# LED_ARRAY.net
KiCad netlist of a schematic drawn in Altium Designer
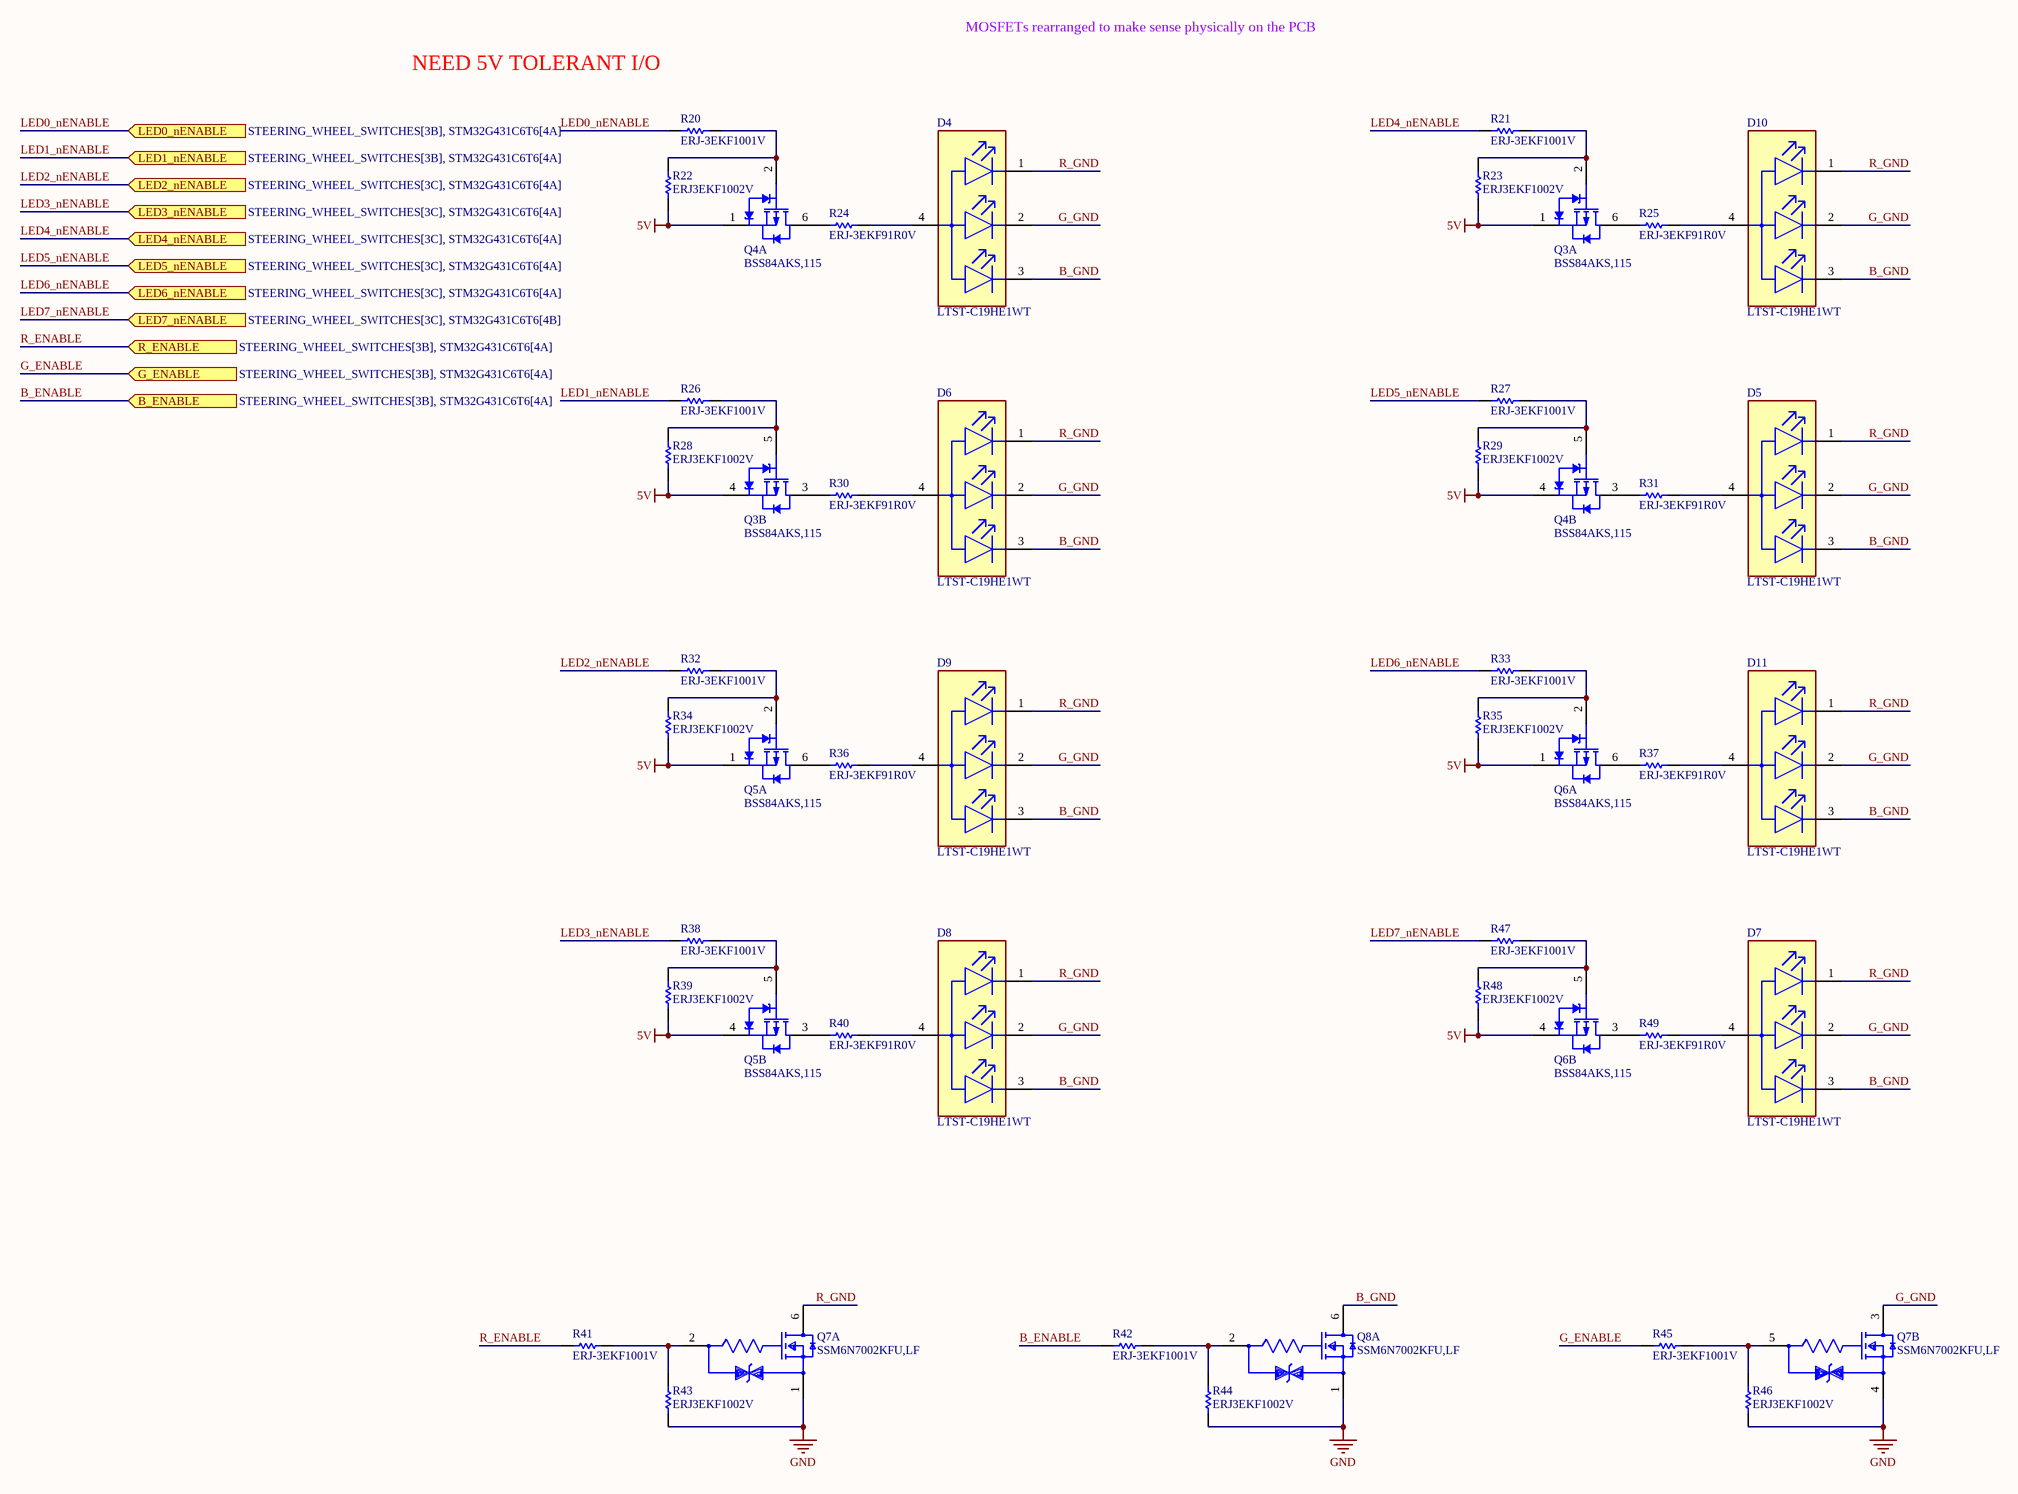
[diagram p0: LED_ARRAY.SchDoc]

(export (version "E")
  (design (tool "Eeschema 10.0.6"))
  (components
    (comp (ref "D4")
      (value "LTST-C19HE1WT")
      (footprint "FP-LTST-C19HE1WT-MFG")
      (description "LED RGB DIFFUSED CHIP SMD")
      (libsource (lib "Altium Content Vault") (part "2c4e1fdd461916b293eda504ca5a2b6"))
    )
    (comp (ref "D5")
      (value "LTST-C19HE1WT")
      (footprint "FP-LTST-C19HE1WT-MFG")
      (description "LED RGB DIFFUSED CHIP SMD")
      (libsource (lib "Altium Content Vault") (part "2c4e1fdd461916b293eda504ca5a2b6"))
    )
    (comp (ref "D6")
      (value "LTST-C19HE1WT")
      (footprint "FP-LTST-C19HE1WT-MFG")
      (description "LED RGB DIFFUSED CHIP SMD")
      (libsource (lib "Altium Content Vault") (part "2c4e1fdd461916b293eda504ca5a2b6"))
    )
    (comp (ref "D7")
      (value "LTST-C19HE1WT")
      (footprint "FP-LTST-C19HE1WT-MFG")
      (description "LED RGB DIFFUSED CHIP SMD")
      (libsource (lib "Altium Content Vault") (part "2c4e1fdd461916b293eda504ca5a2b6"))
    )
    (comp (ref "D8")
      (value "LTST-C19HE1WT")
      (footprint "FP-LTST-C19HE1WT-MFG")
      (description "LED RGB DIFFUSED CHIP SMD")
      (libsource (lib "Altium Content Vault") (part "2c4e1fdd461916b293eda504ca5a2b6"))
    )
    (comp (ref "D9")
      (value "LTST-C19HE1WT")
      (footprint "FP-LTST-C19HE1WT-MFG")
      (description "LED RGB DIFFUSED CHIP SMD")
      (libsource (lib "Altium Content Vault") (part "2c4e1fdd461916b293eda504ca5a2b6"))
    )
    (comp (ref "D10")
      (value "LTST-C19HE1WT")
      (footprint "FP-LTST-C19HE1WT-MFG")
      (description "LED RGB DIFFUSED CHIP SMD")
      (libsource (lib "Altium Content Vault") (part "2c4e1fdd461916b293eda504ca5a2b6"))
    )
    (comp (ref "D11")
      (value "LTST-C19HE1WT")
      (footprint "FP-LTST-C19HE1WT-MFG")
      (description "LED RGB DIFFUSED CHIP SMD")
      (libsource (lib "Altium Content Vault") (part "2c4e1fdd461916b293eda504ca5a2b6"))
    )
    (comp (ref "Q3")
      (value "BSS84AKS,115")
      (footprint "NXP-SOT363_L")
      (description "Dual P-Channel Trench MOSFET, -50 V, -0.16 A, -55 to 150 degC, 6-Pin SOT363, Tape and Reel")
      (fields (field (name "MANUFACTURER") "NXP Semiconductors"))
      (libsource (lib "Altium Content Vault") (part "NXP-PPMOS-SGDSGD-6_A"))
    )
    (comp (ref "Q4")
      (value "BSS84AKS,115")
      (footprint "NXP-SOT363_L")
      (description "Dual P-Channel Trench MOSFET, -50 V, -0.16 A, -55 to 150 degC, 6-Pin SOT363, Tape and Reel")
      (fields (field (name "MANUFACTURER") "NXP Semiconductors"))
      (libsource (lib "Altium Content Vault") (part "NXP-PPMOS-SGDSGD-6_A"))
    )
    (comp (ref "Q5")
      (value "BSS84AKS,115")
      (footprint "NXP-SOT363_L")
      (description "Dual P-Channel Trench MOSFET, -50 V, -0.16 A, -55 to 150 degC, 6-Pin SOT363, Tape and Reel")
      (fields (field (name "MANUFACTURER") "NXP Semiconductors"))
      (libsource (lib "Altium Content Vault") (part "NXP-PPMOS-SGDSGD-6_A"))
    )
    (comp (ref "Q6")
      (value "BSS84AKS,115")
      (footprint "NXP-SOT363_L")
      (description "Dual P-Channel Trench MOSFET, -50 V, -0.16 A, -55 to 150 degC, 6-Pin SOT363, Tape and Reel")
      (fields (field (name "MANUFACTURER") "NXP Semiconductors"))
      (libsource (lib "Altium Content Vault") (part "NXP-PPMOS-SGDSGD-6_A"))
    )
    (comp (ref "Q7")
      (value "SSM6N7002KFU,LF")
      (footprint "FP-SSOP6-P-0_65A-MFG")
      (description "MOSFET 2N-CH 60V 0.3A")
      (libsource (lib "Altium Content Vault") (part "088aa6ac103fdeebe0d1c52ece6b7b9"))
    )
    (comp (ref "Q8")
      (value "SSM6N7002KFU,LF")
      (footprint "FP-SSOP6-P-0_65A-MFG")
      (description "MOSFET 2N-CH 60V 0.3A")
      (libsource (lib "Altium Content Vault") (part "088aa6ac103fdeebe0d1c52ece6b7b9"))
    )
    (comp (ref "R20")
      (value "ERJ-3EKF1001V")
      (footprint "RESC1608X55X30LL15T15")
      (fields (field (name "MANUFACTURER") "Panasonic"))
      (libsource (lib "Altium Content Vault") (part "RES"))
    )
    (comp (ref "R21")
      (value "ERJ-3EKF1001V")
      (footprint "RESC1608X55X30LL15T15")
      (fields (field (name "MANUFACTURER") "Panasonic"))
      (libsource (lib "Altium Content Vault") (part "RES"))
    )
    (comp (ref "R22")
      (value "ERJ3EKF1002V")
      (footprint "RESC1609X55X30LL15T15")
      (description "Chip Resistor, 10 KOhm, +/- 1%, 0.1 W, -55 to 155 degC, 0603 (1608 Metric), RoHS, Tape and Reel")
      (fields (field (name "TOLERANCE") "1%") (field (name "MANUFACTURER") "Panasonic"))
      (libsource (lib "Altium Content Vault") (part "RES-2"))
    )
    (comp (ref "R23")
      (value "ERJ3EKF1002V")
      (footprint "RESC1609X55X30LL15T15")
      (description "Chip Resistor, 10 KOhm, +/- 1%, 0.1 W, -55 to 155 degC, 0603 (1608 Metric), RoHS, Tape and Reel")
      (fields (field (name "TOLERANCE") "1%") (field (name "MANUFACTURER") "Panasonic"))
      (libsource (lib "Altium Content Vault") (part "RES-2"))
    )
    (comp (ref "R24")
      (value "ERJ-3EKF91R0V")
      (footprint "RESC1608X55X30NL15T15")
      (fields (field (name "MANUFACTURER") "Panasonic"))
      (libsource (lib "Altium Content Vault") (part "RES"))
    )
    (comp (ref "R25")
      (value "ERJ-3EKF91R0V")
      (footprint "RESC1608X55X30NL15T15")
      (fields (field (name "MANUFACTURER") "Panasonic"))
      (libsource (lib "Altium Content Vault") (part "RES"))
    )
    (comp (ref "R26")
      (value "ERJ-3EKF1001V")
      (footprint "RESC1608X55X30LL15T15")
      (fields (field (name "MANUFACTURER") "Panasonic"))
      (libsource (lib "Altium Content Vault") (part "RES"))
    )
    (comp (ref "R27")
      (value "ERJ-3EKF1001V")
      (footprint "RESC1608X55X30LL15T15")
      (fields (field (name "MANUFACTURER") "Panasonic"))
      (libsource (lib "Altium Content Vault") (part "RES"))
    )
    (comp (ref "R28")
      (value "ERJ3EKF1002V")
      (footprint "RESC1609X55X30LL15T15")
      (description "Chip Resistor, 10 KOhm, +/- 1%, 0.1 W, -55 to 155 degC, 0603 (1608 Metric), RoHS, Tape and Reel")
      (fields (field (name "TOLERANCE") "1%") (field (name "MANUFACTURER") "Panasonic"))
      (libsource (lib "Altium Content Vault") (part "RES-2"))
    )
    (comp (ref "R29")
      (value "ERJ3EKF1002V")
      (footprint "RESC1609X55X30LL15T15")
      (description "Chip Resistor, 10 KOhm, +/- 1%, 0.1 W, -55 to 155 degC, 0603 (1608 Metric), RoHS, Tape and Reel")
      (fields (field (name "TOLERANCE") "1%") (field (name "MANUFACTURER") "Panasonic"))
      (libsource (lib "Altium Content Vault") (part "RES-2"))
    )
    (comp (ref "R30")
      (value "ERJ-3EKF91R0V")
      (footprint "RESC1608X55X30NL15T15")
      (fields (field (name "MANUFACTURER") "Panasonic"))
      (libsource (lib "Altium Content Vault") (part "RES"))
    )
    (comp (ref "R31")
      (value "ERJ-3EKF91R0V")
      (footprint "RESC1608X55X30NL15T15")
      (fields (field (name "MANUFACTURER") "Panasonic"))
      (libsource (lib "Altium Content Vault") (part "RES"))
    )
    (comp (ref "R32")
      (value "ERJ-3EKF1001V")
      (footprint "RESC1608X55X30LL15T15")
      (fields (field (name "MANUFACTURER") "Panasonic"))
      (libsource (lib "Altium Content Vault") (part "RES"))
    )
    (comp (ref "R33")
      (value "ERJ-3EKF1001V")
      (footprint "RESC1608X55X30LL15T15")
      (fields (field (name "MANUFACTURER") "Panasonic"))
      (libsource (lib "Altium Content Vault") (part "RES"))
    )
    (comp (ref "R34")
      (value "ERJ3EKF1002V")
      (footprint "RESC1609X55X30LL15T15")
      (description "Chip Resistor, 10 KOhm, +/- 1%, 0.1 W, -55 to 155 degC, 0603 (1608 Metric), RoHS, Tape and Reel")
      (fields (field (name "TOLERANCE") "1%") (field (name "MANUFACTURER") "Panasonic"))
      (libsource (lib "Altium Content Vault") (part "RES-2"))
    )
    (comp (ref "R35")
      (value "ERJ3EKF1002V")
      (footprint "RESC1609X55X30LL15T15")
      (description "Chip Resistor, 10 KOhm, +/- 1%, 0.1 W, -55 to 155 degC, 0603 (1608 Metric), RoHS, Tape and Reel")
      (fields (field (name "TOLERANCE") "1%") (field (name "MANUFACTURER") "Panasonic"))
      (libsource (lib "Altium Content Vault") (part "RES-2"))
    )
    (comp (ref "R36")
      (value "ERJ-3EKF91R0V")
      (footprint "RESC1608X55X30NL15T15")
      (fields (field (name "MANUFACTURER") "Panasonic"))
      (libsource (lib "Altium Content Vault") (part "RES"))
    )
    (comp (ref "R37")
      (value "ERJ-3EKF91R0V")
      (footprint "RESC1608X55X30NL15T15")
      (fields (field (name "MANUFACTURER") "Panasonic"))
      (libsource (lib "Altium Content Vault") (part "RES"))
    )
    (comp (ref "R38")
      (value "ERJ-3EKF1001V")
      (footprint "RESC1608X55X30LL15T15")
      (fields (field (name "MANUFACTURER") "Panasonic"))
      (libsource (lib "Altium Content Vault") (part "RES"))
    )
    (comp (ref "R39")
      (value "ERJ3EKF1002V")
      (footprint "RESC1609X55X30LL15T15")
      (description "Chip Resistor, 10 KOhm, +/- 1%, 0.1 W, -55 to 155 degC, 0603 (1608 Metric), RoHS, Tape and Reel")
      (fields (field (name "TOLERANCE") "1%") (field (name "MANUFACTURER") "Panasonic"))
      (libsource (lib "Altium Content Vault") (part "RES-2"))
    )
    (comp (ref "R40")
      (value "ERJ-3EKF91R0V")
      (footprint "RESC1608X55X30NL15T15")
      (fields (field (name "MANUFACTURER") "Panasonic"))
      (libsource (lib "Altium Content Vault") (part "RES"))
    )
    (comp (ref "R41")
      (value "ERJ-3EKF1001V")
      (footprint "RESC1608X55X30LL15T15")
      (fields (field (name "MANUFACTURER") "Panasonic"))
      (libsource (lib "Altium Content Vault") (part "RES"))
    )
    (comp (ref "R42")
      (value "ERJ-3EKF1001V")
      (footprint "RESC1608X55X30LL15T15")
      (fields (field (name "MANUFACTURER") "Panasonic"))
      (libsource (lib "Altium Content Vault") (part "RES"))
    )
    (comp (ref "R43")
      (value "ERJ3EKF1002V")
      (footprint "RESC1609X55X30LL15T15")
      (description "Chip Resistor, 10 KOhm, +/- 1%, 0.1 W, -55 to 155 degC, 0603 (1608 Metric), RoHS, Tape and Reel")
      (fields (field (name "TOLERANCE") "1%") (field (name "MANUFACTURER") "Panasonic"))
      (libsource (lib "Altium Content Vault") (part "RES-2"))
    )
    (comp (ref "R44")
      (value "ERJ3EKF1002V")
      (footprint "RESC1609X55X30LL15T15")
      (description "Chip Resistor, 10 KOhm, +/- 1%, 0.1 W, -55 to 155 degC, 0603 (1608 Metric), RoHS, Tape and Reel")
      (fields (field (name "TOLERANCE") "1%") (field (name "MANUFACTURER") "Panasonic"))
      (libsource (lib "Altium Content Vault") (part "RES-2"))
    )
    (comp (ref "R45")
      (value "ERJ-3EKF1001V")
      (footprint "RESC1608X55X30LL15T15")
      (fields (field (name "MANUFACTURER") "Panasonic"))
      (libsource (lib "Altium Content Vault") (part "RES"))
    )
    (comp (ref "R46")
      (value "ERJ3EKF1002V")
      (footprint "RESC1609X55X30LL15T15")
      (description "Chip Resistor, 10 KOhm, +/- 1%, 0.1 W, -55 to 155 degC, 0603 (1608 Metric), RoHS, Tape and Reel")
      (fields (field (name "TOLERANCE") "1%") (field (name "MANUFACTURER") "Panasonic"))
      (libsource (lib "Altium Content Vault") (part "RES-2"))
    )
    (comp (ref "R47")
      (value "ERJ-3EKF1001V")
      (footprint "RESC1608X55X30LL15T15")
      (fields (field (name "MANUFACTURER") "Panasonic"))
      (libsource (lib "Altium Content Vault") (part "RES"))
    )
    (comp (ref "R48")
      (value "ERJ3EKF1002V")
      (footprint "RESC1609X55X30LL15T15")
      (description "Chip Resistor, 10 KOhm, +/- 1%, 0.1 W, -55 to 155 degC, 0603 (1608 Metric), RoHS, Tape and Reel")
      (fields (field (name "TOLERANCE") "1%") (field (name "MANUFACTURER") "Panasonic"))
      (libsource (lib "Altium Content Vault") (part "RES-2"))
    )
    (comp (ref "R49")
      (value "ERJ-3EKF91R0V")
      (footprint "RESC1608X55X30NL15T15")
      (fields (field (name "MANUFACTURER") "Panasonic"))
      (libsource (lib "Altium Content Vault") (part "RES"))
    )
  )
  (nets
    (net (code "1") (name "/B_ENABLE") (class "Default")
      (node (ref "R42") (pin "1") (pinfunction "1_1") (pintype "passive"))
    )
    (net (code "2") (name "/B_GND") (class "Default")
      (node (ref "D10") (pin "3") (pinfunction "BLUE_C_3") (pintype "passive"))
      (node (ref "D11") (pin "3") (pinfunction "BLUE_C_3") (pintype "passive"))
      (node (ref "D4") (pin "3") (pinfunction "BLUE_C_3") (pintype "passive"))
      (node (ref "D5") (pin "3") (pinfunction "BLUE_C_3") (pintype "passive"))
      (node (ref "D6") (pin "3") (pinfunction "BLUE_C_3") (pintype "passive"))
      (node (ref "D7") (pin "3") (pinfunction "BLUE_C_3") (pintype "passive"))
      (node (ref "D8") (pin "3") (pinfunction "BLUE_C_3") (pintype "passive"))
      (node (ref "D9") (pin "3") (pinfunction "BLUE_C_3") (pintype "passive"))
      (node (ref "Q8") (pin "6") (pinfunction "Drain1_6") (pintype "passive"))
    )
    (net (code "3") (name "/G_ENABLE") (class "Default")
      (node (ref "R45") (pin "1") (pinfunction "1_1") (pintype "passive"))
    )
    (net (code "4") (name "/G_GND") (class "Default")
      (node (ref "D10") (pin "2") (pinfunction "GREEN_C_2") (pintype "passive"))
      (node (ref "D11") (pin "2") (pinfunction "GREEN_C_2") (pintype "passive"))
      (node (ref "D4") (pin "2") (pinfunction "GREEN_C_2") (pintype "passive"))
      (node (ref "D5") (pin "2") (pinfunction "GREEN_C_2") (pintype "passive"))
      (node (ref "D6") (pin "2") (pinfunction "GREEN_C_2") (pintype "passive"))
      (node (ref "D7") (pin "2") (pinfunction "GREEN_C_2") (pintype "passive"))
      (node (ref "D8") (pin "2") (pinfunction "GREEN_C_2") (pintype "passive"))
      (node (ref "D9") (pin "2") (pinfunction "GREEN_C_2") (pintype "passive"))
      (node (ref "Q7") (pin "3") (pinfunction "Drain2_3") (pintype "passive"))
    )
    (net (code "5") (name "/LED0_nENABLE") (class "Default")
      (node (ref "R20") (pin "1") (pinfunction "1_1") (pintype "passive"))
    )
    (net (code "6") (name "/LED1_nENABLE") (class "Default")
      (node (ref "R26") (pin "1") (pinfunction "1_1") (pintype "passive"))
    )
    (net (code "7") (name "/LED2_nENABLE") (class "Default")
      (node (ref "R32") (pin "1") (pinfunction "1_1") (pintype "passive"))
    )
    (net (code "8") (name "/LED3_nENABLE") (class "Default")
      (node (ref "R38") (pin "1") (pinfunction "1_1") (pintype "passive"))
    )
    (net (code "9") (name "/LED4_nENABLE") (class "Default")
      (node (ref "R21") (pin "1") (pinfunction "1_1") (pintype "passive"))
    )
    (net (code "10") (name "/LED5_nENABLE") (class "Default")
      (node (ref "R27") (pin "1") (pinfunction "1_1") (pintype "passive"))
    )
    (net (code "11") (name "/LED6_nENABLE") (class "Default")
      (node (ref "R33") (pin "1") (pinfunction "1_1") (pintype "passive"))
    )
    (net (code "12") (name "/LED7_nENABLE") (class "Default")
      (node (ref "R47") (pin "1") (pinfunction "1_1") (pintype "passive"))
    )
    (net (code "13") (name "/R_ENABLE") (class "Default")
      (node (ref "R41") (pin "1") (pinfunction "1_1") (pintype "passive"))
    )
    (net (code "14") (name "/R_GND") (class "Default")
      (node (ref "D10") (pin "1") (pinfunction "RED_C_1") (pintype "passive"))
      (node (ref "D11") (pin "1") (pinfunction "RED_C_1") (pintype "passive"))
      (node (ref "D4") (pin "1") (pinfunction "RED_C_1") (pintype "passive"))
      (node (ref "D5") (pin "1") (pinfunction "RED_C_1") (pintype "passive"))
      (node (ref "D6") (pin "1") (pinfunction "RED_C_1") (pintype "passive"))
      (node (ref "D7") (pin "1") (pinfunction "RED_C_1") (pintype "passive"))
      (node (ref "D8") (pin "1") (pinfunction "RED_C_1") (pintype "passive"))
      (node (ref "D9") (pin "1") (pinfunction "RED_C_1") (pintype "passive"))
      (node (ref "Q7") (pin "6") (pinfunction "Drain1_6") (pintype "passive"))
    )
    (net (code "15") (name "5V") (class "Default")
      (node (ref "Q3") (pin "1") (pinfunction "S1_1") (pintype "passive"))
      (node (ref "Q3") (pin "4") (pinfunction "S2_4") (pintype "passive"))
      (node (ref "Q4") (pin "1") (pinfunction "S1_1") (pintype "passive"))
      (node (ref "Q4") (pin "4") (pinfunction "S2_4") (pintype "passive"))
      (node (ref "Q5") (pin "1") (pinfunction "S1_1") (pintype "passive"))
      (node (ref "Q5") (pin "4") (pinfunction "S2_4") (pintype "passive"))
      (node (ref "Q6") (pin "1") (pinfunction "S1_1") (pintype "passive"))
      (node (ref "Q6") (pin "4") (pinfunction "S2_4") (pintype "passive"))
      (node (ref "R22") (pin "1") (pinfunction "1_1") (pintype "passive"))
      (node (ref "R23") (pin "1") (pinfunction "1_1") (pintype "passive"))
      (node (ref "R28") (pin "1") (pinfunction "1_1") (pintype "passive"))
      (node (ref "R29") (pin "1") (pinfunction "1_1") (pintype "passive"))
      (node (ref "R34") (pin "1") (pinfunction "1_1") (pintype "passive"))
      (node (ref "R35") (pin "1") (pinfunction "1_1") (pintype "passive"))
      (node (ref "R39") (pin "1") (pinfunction "1_1") (pintype "passive"))
      (node (ref "R48") (pin "1") (pinfunction "1_1") (pintype "passive"))
    )
    (net (code "16") (name "GND") (class "Default")
      (node (ref "Q7") (pin "1") (pinfunction "Source1_1") (pintype "passive"))
      (node (ref "Q7") (pin "4") (pinfunction "Source2_4") (pintype "passive"))
      (node (ref "Q8") (pin "1") (pinfunction "Source1_1") (pintype "passive"))
      (node (ref "R43") (pin "1") (pinfunction "1_1") (pintype "passive"))
      (node (ref "R44") (pin "1") (pinfunction "1_1") (pintype "passive"))
      (node (ref "R46") (pin "1") (pinfunction "1_1") (pintype "passive"))
    )
    (net (code "17") (name "Net-(D4-A)") (class "Default")
      (node (ref "D4") (pin "4") (pinfunction "A_4") (pintype "passive"))
      (node (ref "R24") (pin "2") (pinfunction "2_2") (pintype "passive"))
    )
    (net (code "18") (name "Net-(D5-A)") (class "Default")
      (node (ref "D5") (pin "4") (pinfunction "A_4") (pintype "passive"))
      (node (ref "R31") (pin "2") (pinfunction "2_2") (pintype "passive"))
    )
    (net (code "19") (name "Net-(D6-A)") (class "Default")
      (node (ref "D6") (pin "4") (pinfunction "A_4") (pintype "passive"))
      (node (ref "R30") (pin "2") (pinfunction "2_2") (pintype "passive"))
    )
    (net (code "20") (name "Net-(D7-A)") (class "Default")
      (node (ref "D7") (pin "4") (pinfunction "A_4") (pintype "passive"))
      (node (ref "R49") (pin "2") (pinfunction "2_2") (pintype "passive"))
    )
    (net (code "21") (name "Net-(D8-A)") (class "Default")
      (node (ref "D8") (pin "4") (pinfunction "A_4") (pintype "passive"))
      (node (ref "R40") (pin "2") (pinfunction "2_2") (pintype "passive"))
    )
    (net (code "22") (name "Net-(D9-A)") (class "Default")
      (node (ref "D9") (pin "4") (pinfunction "A_4") (pintype "passive"))
      (node (ref "R36") (pin "2") (pinfunction "2_2") (pintype "passive"))
    )
    (net (code "23") (name "Net-(D10-A)") (class "Default")
      (node (ref "D10") (pin "4") (pinfunction "A_4") (pintype "passive"))
      (node (ref "R25") (pin "2") (pinfunction "2_2") (pintype "passive"))
    )
    (net (code "24") (name "Net-(D11-A)") (class "Default")
      (node (ref "D11") (pin "4") (pinfunction "A_4") (pintype "passive"))
      (node (ref "R37") (pin "2") (pinfunction "2_2") (pintype "passive"))
    )
    (net (code "25") (name "Net-(Q3A-D1)") (class "Default")
      (node (ref "Q3") (pin "6") (pinfunction "D1_6") (pintype "passive"))
      (node (ref "R25") (pin "1") (pinfunction "1_1") (pintype "passive"))
    )
    (net (code "26") (name "Net-(Q3A-G1)") (class "Default")
      (node (ref "Q3") (pin "2") (pinfunction "G1_2") (pintype "passive"))
      (node (ref "R21") (pin "2") (pinfunction "2_2") (pintype "passive"))
      (node (ref "R23") (pin "2") (pinfunction "2_2") (pintype "passive"))
    )
    (net (code "27") (name "Net-(Q3B-D2)") (class "Default")
      (node (ref "Q3") (pin "3") (pinfunction "D2_3") (pintype "passive"))
      (node (ref "R30") (pin "1") (pinfunction "1_1") (pintype "passive"))
    )
    (net (code "28") (name "Net-(Q3B-G2)") (class "Default")
      (node (ref "Q3") (pin "5") (pinfunction "G2_5") (pintype "passive"))
      (node (ref "R26") (pin "2") (pinfunction "2_2") (pintype "passive"))
      (node (ref "R28") (pin "2") (pinfunction "2_2") (pintype "passive"))
    )
    (net (code "29") (name "Net-(Q4A-D1)") (class "Default")
      (node (ref "Q4") (pin "6") (pinfunction "D1_6") (pintype "passive"))
      (node (ref "R24") (pin "1") (pinfunction "1_1") (pintype "passive"))
    )
    (net (code "30") (name "Net-(Q4A-G1)") (class "Default")
      (node (ref "Q4") (pin "2") (pinfunction "G1_2") (pintype "passive"))
      (node (ref "R20") (pin "2") (pinfunction "2_2") (pintype "passive"))
      (node (ref "R22") (pin "2") (pinfunction "2_2") (pintype "passive"))
    )
    (net (code "31") (name "Net-(Q4B-D2)") (class "Default")
      (node (ref "Q4") (pin "3") (pinfunction "D2_3") (pintype "passive"))
      (node (ref "R31") (pin "1") (pinfunction "1_1") (pintype "passive"))
    )
    (net (code "32") (name "Net-(Q4B-G2)") (class "Default")
      (node (ref "Q4") (pin "5") (pinfunction "G2_5") (pintype "passive"))
      (node (ref "R27") (pin "2") (pinfunction "2_2") (pintype "passive"))
      (node (ref "R29") (pin "2") (pinfunction "2_2") (pintype "passive"))
    )
    (net (code "33") (name "Net-(Q5A-D1)") (class "Default")
      (node (ref "Q5") (pin "6") (pinfunction "D1_6") (pintype "passive"))
      (node (ref "R36") (pin "1") (pinfunction "1_1") (pintype "passive"))
    )
    (net (code "34") (name "Net-(Q5A-G1)") (class "Default")
      (node (ref "Q5") (pin "2") (pinfunction "G1_2") (pintype "passive"))
      (node (ref "R32") (pin "2") (pinfunction "2_2") (pintype "passive"))
      (node (ref "R34") (pin "2") (pinfunction "2_2") (pintype "passive"))
    )
    (net (code "35") (name "Net-(Q5B-D2)") (class "Default")
      (node (ref "Q5") (pin "3") (pinfunction "D2_3") (pintype "passive"))
      (node (ref "R40") (pin "1") (pinfunction "1_1") (pintype "passive"))
    )
    (net (code "36") (name "Net-(Q5B-G2)") (class "Default")
      (node (ref "Q5") (pin "5") (pinfunction "G2_5") (pintype "passive"))
      (node (ref "R38") (pin "2") (pinfunction "2_2") (pintype "passive"))
      (node (ref "R39") (pin "2") (pinfunction "2_2") (pintype "passive"))
    )
    (net (code "37") (name "Net-(Q6A-D1)") (class "Default")
      (node (ref "Q6") (pin "6") (pinfunction "D1_6") (pintype "passive"))
      (node (ref "R37") (pin "1") (pinfunction "1_1") (pintype "passive"))
    )
    (net (code "38") (name "Net-(Q6A-G1)") (class "Default")
      (node (ref "Q6") (pin "2") (pinfunction "G1_2") (pintype "passive"))
      (node (ref "R33") (pin "2") (pinfunction "2_2") (pintype "passive"))
      (node (ref "R35") (pin "2") (pinfunction "2_2") (pintype "passive"))
    )
    (net (code "39") (name "Net-(Q6B-D2)") (class "Default")
      (node (ref "Q6") (pin "3") (pinfunction "D2_3") (pintype "passive"))
      (node (ref "R49") (pin "1") (pinfunction "1_1") (pintype "passive"))
    )
    (net (code "40") (name "Net-(Q6B-G2)") (class "Default")
      (node (ref "Q6") (pin "5") (pinfunction "G2_5") (pintype "passive"))
      (node (ref "R47") (pin "2") (pinfunction "2_2") (pintype "passive"))
      (node (ref "R48") (pin "2") (pinfunction "2_2") (pintype "passive"))
    )
    (net (code "41") (name "Net-(Q7A-Gate1)") (class "Default")
      (node (ref "Q7") (pin "2") (pinfunction "Gate1_2") (pintype "passive"))
      (node (ref "R41") (pin "2") (pinfunction "2_2") (pintype "passive"))
      (node (ref "R43") (pin "2") (pinfunction "2_2") (pintype "passive"))
    )
    (net (code "42") (name "Net-(Q7B-Gate2)") (class "Default")
      (node (ref "Q7") (pin "5") (pinfunction "Gate2_5") (pintype "passive"))
      (node (ref "R45") (pin "2") (pinfunction "2_2") (pintype "passive"))
      (node (ref "R46") (pin "2") (pinfunction "2_2") (pintype "passive"))
    )
    (net (code "43") (name "Net-(Q8A-Gate1)") (class "Default")
      (node (ref "Q8") (pin "2") (pinfunction "Gate1_2") (pintype "passive"))
      (node (ref "R42") (pin "2") (pinfunction "2_2") (pintype "passive"))
      (node (ref "R44") (pin "2") (pinfunction "2_2") (pintype "passive"))
    )
  )
)
